# System_critical_signals_PCB.net
KiCad netlist of a schematic drawn in EAGLE
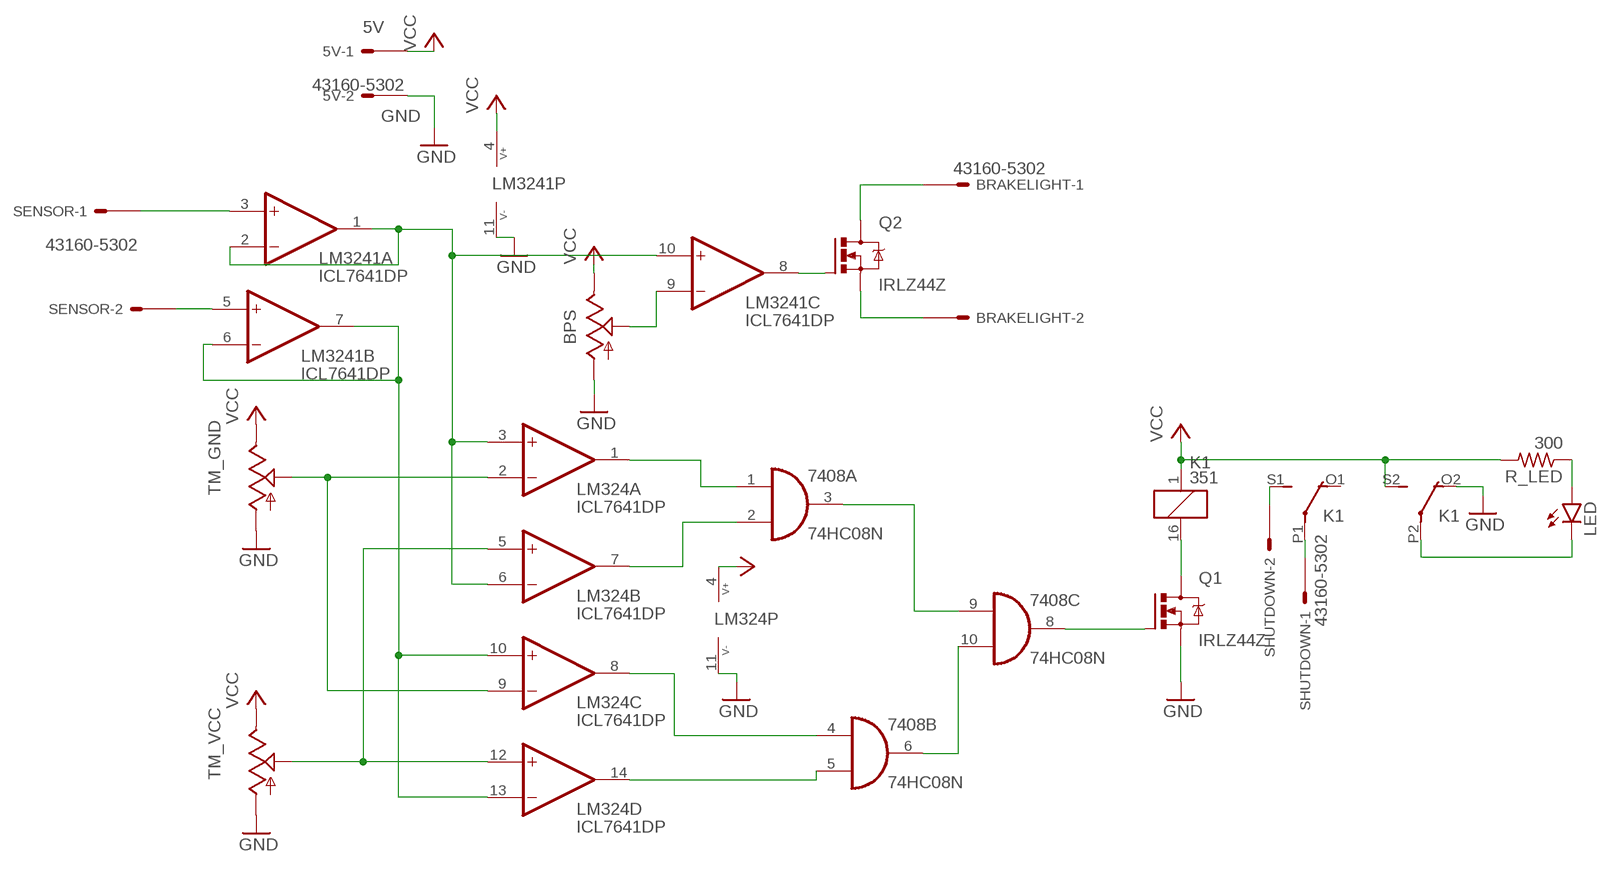
[diagram p0: schematic, sheet 1]

(export (version "E")
  (design (tool "Eeschema 10.0.6"))
  (components
    (comp (ref "5V")
      (value "43160-5302")
      (footprint "eagle-import:43160-XX02")
      (fields (field (name "MF") "MOLEX"))
      (libsource (lib "eagle-import") (part "43160-0253"))
    )
    (comp (ref "7408")
      (value "74HC08N")
      (footprint "eagle-import:DIL14")
      (libsource (lib "eagle-import") (part "7408NHC"))
    )
    (comp (ref "BPS")
      (value "TRIM")
      (footprint "eagle-import:6MM")
      (libsource (lib "eagle-import") (part "TRIM"))
    )
    (comp (ref "BRAKELIGHT")
      (value "43160-5302")
      (footprint "eagle-import:43160-XX02")
      (fields (field (name "MF") "MOLEX"))
      (libsource (lib "eagle-import") (part "43160-0253"))
    )
    (comp (ref "K1")
      (value "351")
      (footprint "eagle-import:351")
      (libsource (lib "eagle-import") (part "351"))
    )
    (comp (ref "LED")
      (value "LEDCHIP-LED0805")
      (footprint "eagle-import:CHIP-LED0805")
      (libsource (lib "eagle-import") (part "LEDCHIP-LED0805"))
    )
    (comp (ref "LM324")
      (value "ICL7641DP")
      (footprint "eagle-import:DIL14")
      (libsource (lib "eagle-import") (part "ICL764DP1"))
    )
    (comp (ref "LM3241")
      (value "ICL7641DP")
      (footprint "eagle-import:DIL14")
      (libsource (lib "eagle-import") (part "ICL764DP1"))
    )
    (comp (ref "Q1")
      (value "IRLZ44Z")
      (footprint "eagle-import:TO220BH")
      (libsource (lib "eagle-import") (part "IRLZ44Z"))
    )
    (comp (ref "Q2")
      (value "IRLZ44Z")
      (footprint "eagle-import:TO220BH")
      (libsource (lib "eagle-import") (part "IRLZ44Z"))
    )
    (comp (ref "R_LED")
      (value "300")
      (footprint "eagle-import:M0805")
      (libsource (lib "eagle-import") (part "R-US_M0805"))
    )
    (comp (ref "SENSOR")
      (value "43160-5302")
      (footprint "eagle-import:43160-XX02")
      (fields (field (name "MF") "MOLEX"))
      (libsource (lib "eagle-import") (part "43160-0253"))
    )
    (comp (ref "SHUTDOWN")
      (value "43160-5302")
      (footprint "eagle-import:43160-XX02")
      (fields (field (name "MF") "MOLEX"))
      (libsource (lib "eagle-import") (part "43160-0253"))
    )
    (comp (ref "TM_GND")
      (value "TRIM")
      (footprint "eagle-import:6MM")
      (libsource (lib "eagle-import") (part "TRIM"))
    )
    (comp (ref "TM_VCC")
      (value "TRIM")
      (footprint "eagle-import:6MM")
      (libsource (lib "eagle-import") (part "TRIM"))
    )
  )
  (nets
    (net (code "1") (name "GND") (class "Default")
      (node (ref "5V") (pin "2@1") (pinfunction "S_2@1") (pintype "passive"))
      (node (ref "BPS") (pin "A") (pinfunction "A_A") (pintype "passive"))
      (node (ref "K1") (pin "O2") (pinfunction "O_O2") (pintype "passive"))
      (node (ref "LM324") (pin "11") (pinfunction "V-_11") (pintype "power_in"))
      (node (ref "LM3241") (pin "11") (pinfunction "V-_11") (pintype "power_in"))
      (node (ref "Q1") (pin "S") (pinfunction "S_S") (pintype "passive"))
      (node (ref "TM_GND") (pin "A") (pinfunction "A_A") (pintype "passive"))
      (node (ref "TM_VCC") (pin "A") (pinfunction "A_A") (pintype "passive"))
    )
    (net (code "2") (name "Net-(7408A-I0)") (class "Default")
      (node (ref "7408") (pin "1") (pinfunction "I0_1") (pintype "input"))
      (node (ref "LM324") (pin "1") (pinfunction "OUT_1") (pintype "output"))
    )
    (net (code "3") (name "Net-(7408A-I1)") (class "Default")
      (node (ref "7408") (pin "2") (pinfunction "I1_2") (pintype "input"))
      (node (ref "LM324") (pin "7") (pinfunction "OUT_7") (pintype "output"))
    )
    (net (code "4") (name "Net-(7408A-O)") (class "Default")
      (node (ref "7408") (pin "3") (pinfunction "O_3") (pintype "output"))
      (node (ref "7408") (pin "9") (pinfunction "I0_9") (pintype "input"))
    )
    (net (code "5") (name "Net-(7408B-I0)") (class "Default")
      (node (ref "7408") (pin "4") (pinfunction "I0_4") (pintype "input"))
      (node (ref "LM324") (pin "8") (pinfunction "OUT_8") (pintype "output"))
    )
    (net (code "6") (name "Net-(7408B-I1)") (class "Default")
      (node (ref "7408") (pin "5") (pinfunction "I1_5") (pintype "input"))
      (node (ref "LM324") (pin "14") (pinfunction "OUT_14") (pintype "output"))
    )
    (net (code "7") (name "Net-(7408B-O)") (class "Default")
      (node (ref "7408") (pin "10") (pinfunction "I1_10") (pintype "input"))
      (node (ref "7408") (pin "6") (pinfunction "O_6") (pintype "output"))
    )
    (net (code "8") (name "Net-(7408C-O)") (class "Default")
      (node (ref "7408") (pin "8") (pinfunction "O_8") (pintype "output"))
      (node (ref "Q1") (pin "G") (pinfunction "G_G") (pintype "passive"))
    )
    (net (code "9") (name "Net-(BRAKELIGHTA-S-Pad1@1)") (class "Default")
      (node (ref "BRAKELIGHT") (pin "1@1") (pinfunction "S_1@1") (pintype "passive"))
      (node (ref "Q2") (pin "D") (pinfunction "D_D") (pintype "passive"))
    )
    (net (code "10") (name "Net-(BRAKELIGHTB-S-Pad2@1)") (class "Default")
      (node (ref "BRAKELIGHT") (pin "2@1") (pinfunction "S_2@1") (pintype "passive"))
      (node (ref "Q2") (pin "S") (pinfunction "S_S") (pintype "passive"))
    )
    (net (code "11") (name "Net-(K1A-2)") (class "Default")
      (node (ref "K1") (pin "16") (pinfunction "2_16") (pintype "passive"))
      (node (ref "Q1") (pin "D") (pinfunction "D_D") (pintype "passive"))
    )
    (net (code "12") (name "Net-(K1B-P)") (class "Default")
      (node (ref "K1") (pin "P1") (pinfunction "P_P1") (pintype "passive"))
      (node (ref "SHUTDOWN") (pin "1@1") (pinfunction "S_1@1") (pintype "passive"))
    )
    (net (code "13") (name "Net-(K1B-S)") (class "Default")
      (node (ref "K1") (pin "S1") (pinfunction "S_S1") (pintype "passive"))
      (node (ref "SHUTDOWN") (pin "2@1") (pinfunction "S_2@1") (pintype "passive"))
    )
    (net (code "14") (name "Net-(K1C-P)") (class "Default")
      (node (ref "K1") (pin "P2") (pinfunction "P_P2") (pintype "passive"))
      (node (ref "LED") (pin "C") (pinfunction "C_C") (pintype "passive"))
    )
    (net (code "15") (name "Net-(LED-PadA)") (class "Default")
      (node (ref "LED") (pin "A") (pinfunction "A_A") (pintype "passive"))
      (node (ref "R_LED") (pin "1") (pinfunction "1_1") (pintype "passive"))
    )
    (net (code "16") (name "Net-(LM324A--IN)") (class "Default")
      (node (ref "LM324") (pin "2") (pinfunction "-IN_2") (pintype "input"))
      (node (ref "LM324") (pin "9") (pinfunction "-IN_9") (pintype "input"))
      (node (ref "TM_GND") (pin "S") (pinfunction "S_S") (pintype "passive"))
    )
    (net (code "17") (name "Net-(LM324B-+IN)") (class "Default")
      (node (ref "LM324") (pin "12") (pinfunction "+IN_12") (pintype "input"))
      (node (ref "LM324") (pin "5") (pinfunction "+IN_5") (pintype "input"))
      (node (ref "TM_VCC") (pin "S") (pinfunction "S_S") (pintype "passive"))
    )
    (net (code "18") (name "Net-(LM3241A-+IN)") (class "Default")
      (node (ref "LM3241") (pin "3") (pinfunction "+IN_3") (pintype "input"))
      (node (ref "SENSOR") (pin "1@1") (pinfunction "S_1@1") (pintype "passive"))
    )
    (net (code "19") (name "Net-(LM3241A--IN)") (class "Default")
      (node (ref "LM324") (pin "3") (pinfunction "+IN_3") (pintype "input"))
      (node (ref "LM324") (pin "6") (pinfunction "-IN_6") (pintype "input"))
      (node (ref "LM3241") (pin "1") (pinfunction "OUT_1") (pintype "output"))
      (node (ref "LM3241") (pin "10") (pinfunction "+IN_10") (pintype "input"))
      (node (ref "LM3241") (pin "2") (pinfunction "-IN_2") (pintype "input"))
    )
    (net (code "20") (name "Net-(LM3241B-+IN)") (class "Default")
      (node (ref "LM3241") (pin "5") (pinfunction "+IN_5") (pintype "input"))
      (node (ref "SENSOR") (pin "2@1") (pinfunction "S_2@1") (pintype "passive"))
    )
    (net (code "21") (name "Net-(LM3241B--IN)") (class "Default")
      (node (ref "LM324") (pin "10") (pinfunction "+IN_10") (pintype "input"))
      (node (ref "LM324") (pin "13") (pinfunction "-IN_13") (pintype "input"))
      (node (ref "LM3241") (pin "6") (pinfunction "-IN_6") (pintype "input"))
      (node (ref "LM3241") (pin "7") (pinfunction "OUT_7") (pintype "output"))
    )
    (net (code "22") (name "Net-(LM3241C--IN)") (class "Default")
      (node (ref "BPS") (pin "S") (pinfunction "S_S") (pintype "passive"))
      (node (ref "LM3241") (pin "9") (pinfunction "-IN_9") (pintype "input"))
    )
    (net (code "23") (name "Net-(LM3241C-OUT)") (class "Default")
      (node (ref "LM3241") (pin "8") (pinfunction "OUT_8") (pintype "output"))
      (node (ref "Q2") (pin "G") (pinfunction "G_G") (pintype "passive"))
    )
    (net (code "24") (name "VCC") (class "Default")
      (node (ref "5V") (pin "1@1") (pinfunction "S_1@1") (pintype "passive"))
      (node (ref "BPS") (pin "E") (pinfunction "E_E") (pintype "passive"))
      (node (ref "K1") (pin "1") (pinfunction "1_1") (pintype "passive"))
      (node (ref "K1") (pin "S2") (pinfunction "S_S2") (pintype "passive"))
      (node (ref "LM324") (pin "4") (pinfunction "V+_4") (pintype "power_in"))
      (node (ref "LM3241") (pin "4") (pinfunction "V+_4") (pintype "power_in"))
      (node (ref "R_LED") (pin "2") (pinfunction "2_2") (pintype "passive"))
      (node (ref "TM_GND") (pin "E") (pinfunction "E_E") (pintype "passive"))
      (node (ref "TM_VCC") (pin "E") (pinfunction "E_E") (pintype "passive"))
    )
    (net (code "25") (name "unconnected-(5VA-S-Pad1@2)") (class "Default")
      (node (ref "5V") (pin "1@2") (pinfunction "S_1@2") (pintype "passive"))
    )
    (net (code "26") (name "unconnected-(5VB-S-Pad2@2)") (class "Default")
      (node (ref "5V") (pin "2@2") (pinfunction "S_2@2") (pintype "passive"))
    )
    (net (code "27") (name "unconnected-(BRAKELIGHTA-S-Pad1@2)") (class "Default")
      (node (ref "BRAKELIGHT") (pin "1@2") (pinfunction "S_1@2") (pintype "passive"))
    )
    (net (code "28") (name "unconnected-(BRAKELIGHTB-S-Pad2@2)") (class "Default")
      (node (ref "BRAKELIGHT") (pin "2@2") (pinfunction "S_2@2") (pintype "passive"))
    )
    (net (code "29") (name "unconnected-(K1B-O-PadO1)") (class "Default")
      (node (ref "K1") (pin "O1") (pinfunction "O_O1") (pintype "passive"))
    )
    (net (code "30") (name "unconnected-(SENSORA-S-Pad1@2)") (class "Default")
      (node (ref "SENSOR") (pin "1@2") (pinfunction "S_1@2") (pintype "passive"))
    )
    (net (code "31") (name "unconnected-(SENSORB-S-Pad2@2)") (class "Default")
      (node (ref "SENSOR") (pin "2@2") (pinfunction "S_2@2") (pintype "passive"))
    )
    (net (code "32") (name "unconnected-(SHUTDOWNA-S-Pad1@2)") (class "Default")
      (node (ref "SHUTDOWN") (pin "1@2") (pinfunction "S_1@2") (pintype "passive"))
    )
    (net (code "33") (name "unconnected-(SHUTDOWNB-S-Pad2@2)") (class "Default")
      (node (ref "SHUTDOWN") (pin "2@2") (pinfunction "S_2@2") (pintype "passive"))
    )
  )
)
